# BOC_Spartan.net
KiCad netlist of a schematic drawn in Altium Designer
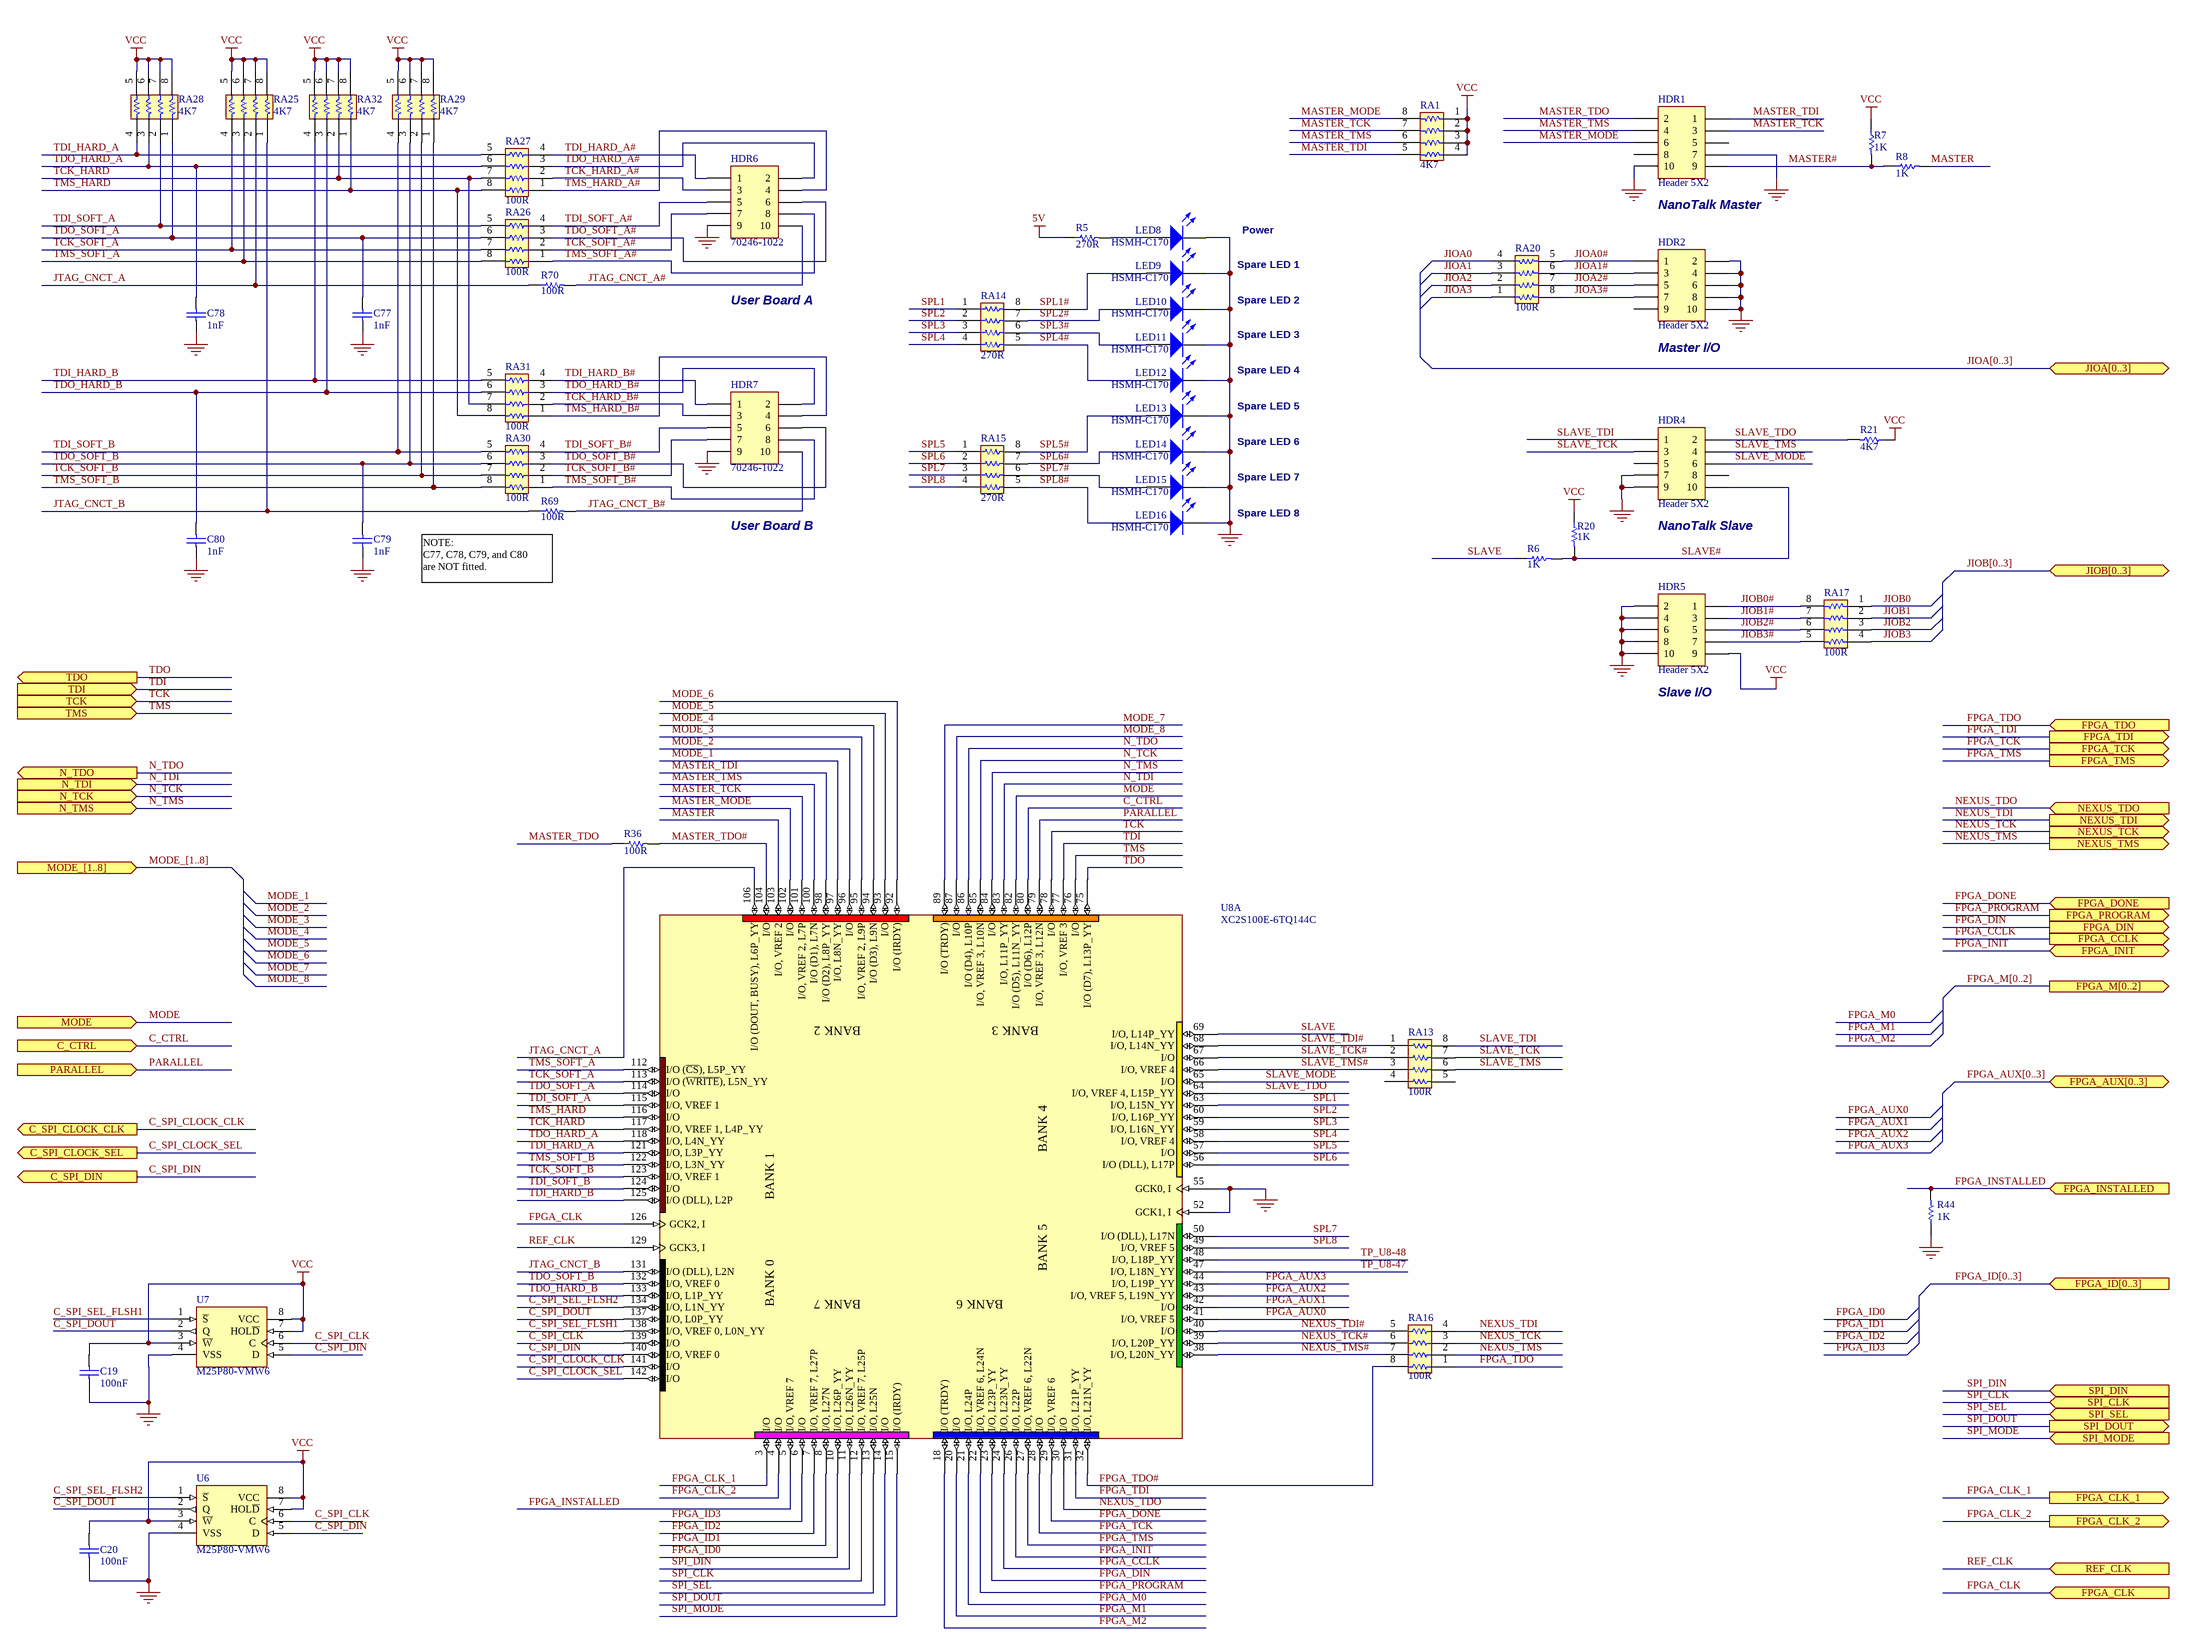
[diagram p0: BOC_Spartan.SchDoc]

(export (version "E")
  (design (tool "Eeschema 10.0.6"))
  (components
    (comp (ref "C19")
      (value "100nF")
      (footprint "Altium Nanoboard Project:CC2012-0805")
      (description "Capacitor")
      (libsource (lib "Altium Nanoboard Project") (part "CAP"))
    )
    (comp (ref "C20")
      (value "100nF")
      (footprint "Altium Nanoboard Project:CC2012-0805")
      (description "Capacitor")
      (libsource (lib "Altium Nanoboard Project") (part "CAP"))
    )
    (comp (ref "C77")
      (value "1nF")
      (footprint "Altium Nanoboard Project:CC2012-0805")
      (description "Capacitor")
      (libsource (lib "Altium Nanoboard Project") (part "CAP"))
    )
    (comp (ref "C78")
      (value "1nF")
      (footprint "Altium Nanoboard Project:CC2012-0805")
      (description "Capacitor")
      (libsource (lib "Altium Nanoboard Project") (part "CAP"))
    )
    (comp (ref "C79")
      (value "1nF")
      (footprint "Altium Nanoboard Project:CC2012-0805")
      (description "Capacitor")
      (libsource (lib "Altium Nanoboard Project") (part "CAP"))
    )
    (comp (ref "C80")
      (value "1nF")
      (footprint "Altium Nanoboard Project:CC2012-0805")
      (description "Capacitor")
      (libsource (lib "Altium Nanoboard Project") (part "CAP"))
    )
    (comp (ref "HDR1")
      (value "Header 5X2")
      (footprint "Altium Nanoboard Project:HDR2X5")
      (description "Header, 5-Pin, Dual row")
      (fields
        (field (name "MANUFACTURER") "Generic Components")
        (field (name "USAGE") "NanoTalk Master")
        (field (name "PUBLISHER") "Altium Limited")
      )
      (libsource (lib "") (part "Header 5X2_1"))
    )
    (comp (ref "HDR2")
      (value "Header 5X2")
      (footprint "Altium Nanoboard Project:HDR2X5")
      (description "Header, 5-Pin, Dual row")
      (fields
        (field (name "MANUFACTURER") "Generic Components")
        (field (name "USAGE") "Master I/O")
        (field (name "PUBLISHER") "Altium Limited")
      )
      (libsource (lib "Altium Nanoboard Project") (part "Header 5X2"))
    )
    (comp (ref "HDR4")
      (value "Header 5X2")
      (footprint "Altium Nanoboard Project:HDR2X5")
      (description "Header, 5-Pin, Dual row")
      (fields
        (field (name "MANUFACTURER") "Generic Components")
        (field (name "USAGE") "NanoTalk Slave")
        (field (name "PUBLISHER") "Altium Limited")
      )
      (libsource (lib "Altium Nanoboard Project") (part "Header 5X2"))
    )
    (comp (ref "HDR5")
      (value "Header 5X2")
      (footprint "Altium Nanoboard Project:HDR2X5")
      (description "Header, 5-Pin, Dual row")
      (fields
        (field (name "MANUFACTURER") "Generic Components")
        (field (name "USAGE") "Slave I/O")
        (field (name "PUBLISHER") "Altium Limited")
      )
      (libsource (lib "") (part "Header 5X2_1"))
    )
    (comp (ref "HDR6")
      (value "70246-1022")
      (footprint "Altium Nanoboard Project:HDR2X5_LP")
      (description "Header, 5-Pin, Dual row")
      (fields
        (field (name "MANUFACTURER") "Molex")
        (field (name "USAGE") "User Board A")
        (field (name "PUBLISHER") "Altium Limited")
      )
      (libsource (lib "Altium Nanoboard Project") (part "Header 5X2"))
    )
    (comp (ref "HDR7")
      (value "70246-1022")
      (footprint "Altium Nanoboard Project:HDR2X5_LP")
      (description "Header, 5-Pin, Dual row")
      (fields
        (field (name "MANUFACTURER") "Molex")
        (field (name "USAGE") "User Board B")
        (field (name "PUBLISHER") "Altium Limited")
      )
      (libsource (lib "Altium Nanoboard Project") (part "Header 5X2"))
    )
    (comp (ref "LED8")
      (value "HSMH-C170")
      (footprint "Altium Nanoboard Project:SMD _LED")
      (description "Typical RED GaAs SMD LED Agilent make")
      (fields (field (name "MANUFACTURER") "Generic Components") (field (name "PUBLISHER") "Altium Limited"))
      (libsource (lib "Altium Nanoboard Project") (part "HSMX-C670"))
    )
    (comp (ref "LED9")
      (value "HSMH-C170")
      (footprint "Altium Nanoboard Project:SMD _LED")
      (description "Typical RED GaAs SMD LED Agilent make")
      (fields (field (name "MANUFACTURER") "Generic Components") (field (name "PUBLISHER") "Altium Limited"))
      (libsource (lib "Altium Nanoboard Project") (part "HSMX-C670"))
    )
    (comp (ref "LED10")
      (value "HSMH-C170")
      (footprint "Altium Nanoboard Project:SMD _LED")
      (description "Typical RED GaAs SMD LED Agilent make")
      (fields (field (name "MANUFACTURER") "Generic Components") (field (name "PUBLISHER") "Altium Limited"))
      (libsource (lib "Altium Nanoboard Project") (part "HSMX-C670"))
    )
    (comp (ref "LED11")
      (value "HSMH-C170")
      (footprint "Altium Nanoboard Project:SMD _LED")
      (description "Typical RED GaAs SMD LED Agilent make")
      (fields (field (name "MANUFACTURER") "Generic Components") (field (name "PUBLISHER") "Altium Limited"))
      (libsource (lib "Altium Nanoboard Project") (part "HSMX-C670"))
    )
    (comp (ref "LED12")
      (value "HSMH-C170")
      (footprint "Altium Nanoboard Project:SMD _LED")
      (description "Typical RED GaAs SMD LED Agilent make")
      (fields (field (name "MANUFACTURER") "Generic Components") (field (name "PUBLISHER") "Altium Limited"))
      (libsource (lib "Altium Nanoboard Project") (part "HSMX-C670"))
    )
    (comp (ref "LED13")
      (value "HSMH-C170")
      (footprint "Altium Nanoboard Project:SMD _LED")
      (description "Typical RED GaAs SMD LED Agilent make")
      (fields (field (name "MANUFACTURER") "Generic Components") (field (name "PUBLISHER") "Altium Limited"))
      (libsource (lib "Altium Nanoboard Project") (part "HSMX-C670"))
    )
    (comp (ref "LED14")
      (value "HSMH-C170")
      (footprint "Altium Nanoboard Project:SMD _LED")
      (description "Typical RED GaAs SMD LED Agilent make")
      (fields (field (name "MANUFACTURER") "Generic Components") (field (name "PUBLISHER") "Altium Limited"))
      (libsource (lib "Altium Nanoboard Project") (part "HSMX-C670"))
    )
    (comp (ref "LED15")
      (value "HSMH-C170")
      (footprint "Altium Nanoboard Project:SMD _LED")
      (description "Typical RED GaAs SMD LED Agilent make")
      (fields (field (name "MANUFACTURER") "Generic Components") (field (name "PUBLISHER") "Altium Limited"))
      (libsource (lib "Altium Nanoboard Project") (part "HSMX-C670"))
    )
    (comp (ref "LED16")
      (value "HSMH-C170")
      (footprint "Altium Nanoboard Project:SMD _LED")
      (description "Typical RED GaAs SMD LED Agilent make")
      (fields (field (name "MANUFACTURER") "Generic Components") (field (name "PUBLISHER") "Altium Limited"))
      (libsource (lib "Altium Nanoboard Project") (part "HSMX-C670"))
    )
    (comp (ref "R5")
      (value "270R")
      (footprint "Altium Nanoboard Project:CC2012-0805")
      (description "Resistor")
      (libsource (lib "Altium Nanoboard Project") (part "RES"))
    )
    (comp (ref "R6")
      (value "1K")
      (footprint "Altium Nanoboard Project:CC2012-0805")
      (description "Resistor")
      (libsource (lib "Altium Nanoboard Project") (part "RES"))
    )
    (comp (ref "R7")
      (value "1K")
      (footprint "Altium Nanoboard Project:CC2012-0805")
      (description "Resistor")
      (libsource (lib "Altium Nanoboard Project") (part "RES"))
    )
    (comp (ref "R8")
      (value "1K")
      (footprint "Altium Nanoboard Project:CC2012-0805")
      (description "Resistor")
      (libsource (lib "") (part "RES_1"))
    )
    (comp (ref "R20")
      (value "1K")
      (footprint "Altium Nanoboard Project:CC2012-0805")
      (description "Resistor")
      (libsource (lib "Altium Nanoboard Project") (part "RES"))
    )
    (comp (ref "R21")
      (value "4K7")
      (footprint "Altium Nanoboard Project:CC2012-0805")
      (description "Resistor")
      (libsource (lib "Altium Nanoboard Project") (part "RES"))
    )
    (comp (ref "R36")
      (value "100R")
      (footprint "Altium Nanoboard Project:CC2012-0805")
      (description "Resistor")
      (libsource (lib "Altium Nanoboard Project") (part "RES"))
    )
    (comp (ref "R44")
      (value "1K")
      (footprint "Altium Nanoboard Project:CC2012-0805")
      (description "Resistor")
      (libsource (lib "Altium Nanoboard Project") (part "RES"))
    )
    (comp (ref "R69")
      (value "100R")
      (footprint "Altium Nanoboard Project:CC2012-0805")
      (description "Resistor")
      (libsource (lib "Altium Nanoboard Project") (part "RES"))
    )
    (comp (ref "R70")
      (value "100R")
      (footprint "Altium Nanoboard Project:CC2012-0805")
      (description "Resistor")
      (libsource (lib "Altium Nanoboard Project") (part "RES"))
    )
    (comp (ref "RA1")
      (value "4K7")
      (footprint "Altium Nanoboard Project:MNR34")
      (description "3216x4 Resistor Array")
      (libsource (lib "") (part "MNR34_3"))
    )
    (comp (ref "RA13")
      (value "100R")
      (footprint "Altium Nanoboard Project:MNR34")
      (description "3216x4 Resistor Array")
      (libsource (lib "") (part "MNR34_2"))
    )
    (comp (ref "RA14")
      (value "270R")
      (footprint "Altium Nanoboard Project:MNR34")
      (description "3216x4 Resistor Array")
      (libsource (lib "") (part "MNR34_2"))
    )
    (comp (ref "RA15")
      (value "270R")
      (footprint "Altium Nanoboard Project:MNR34")
      (description "3216x4 Resistor Array")
      (libsource (lib "") (part "MNR34_2"))
    )
    (comp (ref "RA16")
      (value "100R")
      (footprint "Altium Nanoboard Project:MNR34")
      (description "3216x4 Resistor Array")
      (libsource (lib "Altium Nanoboard Project") (part "MNR34"))
    )
    (comp (ref "RA17")
      (value "100R")
      (footprint "Altium Nanoboard Project:MNR34")
      (description "3216x4 Resistor Array")
      (libsource (lib "") (part "MNR34_3"))
    )
    (comp (ref "RA20")
      (value "100R")
      (footprint "Altium Nanoboard Project:MNR34")
      (description "3216x4 Resistor Array")
      (libsource (lib "") (part "MNR34_4"))
    )
    (comp (ref "RA25")
      (value "4K7")
      (footprint "Altium Nanoboard Project:MNR34")
      (description "3216x4 Resistor Array")
      (libsource (lib "") (part "MNR34_2"))
    )
    (comp (ref "RA26")
      (value "100R")
      (footprint "Altium Nanoboard Project:MNR34")
      (description "3216x4 Resistor Array")
      (libsource (lib "") (part "MNR34_1"))
    )
    (comp (ref "RA27")
      (value "100R")
      (footprint "Altium Nanoboard Project:MNR34")
      (description "3216x4 Resistor Array")
      (libsource (lib "") (part "MNR34_1"))
    )
    (comp (ref "RA28")
      (value "4K7")
      (footprint "Altium Nanoboard Project:MNR34")
      (description "3216x4 Resistor Array")
      (libsource (lib "") (part "MNR34_2"))
    )
    (comp (ref "RA29")
      (value "4K7")
      (footprint "Altium Nanoboard Project:MNR34")
      (description "3216x4 Resistor Array")
      (libsource (lib "") (part "MNR34_2"))
    )
    (comp (ref "RA30")
      (value "100R")
      (footprint "Altium Nanoboard Project:MNR34")
      (description "3216x4 Resistor Array")
      (libsource (lib "") (part "MNR34_1"))
    )
    (comp (ref "RA31")
      (value "100R")
      (footprint "Altium Nanoboard Project:MNR34")
      (description "3216x4 Resistor Array")
      (libsource (lib "") (part "MNR34_1"))
    )
    (comp (ref "RA32")
      (value "4K7")
      (footprint "Altium Nanoboard Project:MNR34")
      (description "3216x4 Resistor Array")
      (libsource (lib "") (part "MNR34_2"))
    )
    (comp (ref "U6")
      (value "M25P80-VMW6")
      (footprint "Altium Nanoboard Project:SO8_MW/SO8_MN")
      (description "8 Mbit Flash Serial Prom")
      (libsource (lib "Altium Nanoboard Project") (part "M25P10-VMN6"))
    )
    (comp (ref "U7")
      (value "M25P80-VMW6")
      (footprint "Altium Nanoboard Project:SO8_MW/SO8_MN")
      (description "8 Mbit Flash Serial Prom")
      (libsource (lib "Altium Nanoboard Project") (part "M25P20-VMN6"))
    )
    (comp (ref "U8")
      (value "XC2S100E-6TQ144C")
      (footprint "Altium Nanoboard Project:TQ144")
      (description "Spartan-IIE 1.8V FPGA, 144-Pin TQFP, Standard Performance, Commercial Grade")
      (fields (field (name "MANUFACTURER") "Xilinx") (field (name "PUBLISHER") "Altium Limited"))
      (libsource (lib "Altium Nanoboard Project") (part "XC2S100E-6TQ144C"))
    )
  )
  (nets
    (net (code "1") (name "/C_CTRL") (class "Default")
      (node (ref "U8") (pin "80") (pinfunction "I/O_(D6),_L12P_80") (pintype "bidirectional"))
    )
    (net (code "2") (name "/C_SPI_CLK") (class "Default")
      (node (ref "U6") (pin "6") (pinfunction "C_6") (pintype "input"))
      (node (ref "U7") (pin "6") (pinfunction "C_6") (pintype "input"))
      (node (ref "U8") (pin "139") (pinfunction "I/O_139") (pintype "bidirectional"))
    )
    (net (code "3") (name "/C_SPI_CLOCK_CLK") (class "Default")
      (node (ref "U8") (pin "141") (pinfunction "I/O_141") (pintype "bidirectional"))
    )
    (net (code "4") (name "/C_SPI_CLOCK_SEL") (class "Default")
      (node (ref "U8") (pin "142") (pinfunction "I/O_142") (pintype "bidirectional"))
    )
    (net (code "5") (name "/C_SPI_DIN") (class "Default")
      (node (ref "U6") (pin "5") (pinfunction "D_5") (pintype "input"))
      (node (ref "U7") (pin "5") (pinfunction "D_5") (pintype "input"))
      (node (ref "U8") (pin "140") (pinfunction "I/O,_VREF_0_140") (pintype "bidirectional"))
    )
    (net (code "6") (name "/C_SPI_DOUT") (class "Default")
      (node (ref "U6") (pin "2") (pinfunction "Q_2") (pintype "output"))
      (node (ref "U7") (pin "2") (pinfunction "Q_2") (pintype "output"))
      (node (ref "U8") (pin "137") (pinfunction "I/O,_L0P_YY_137") (pintype "bidirectional"))
    )
    (net (code "7") (name "/C_SPI_SEL_FLSH1") (class "Default")
      (node (ref "U7") (pin "1") (pinfunction "~{S}_1") (pintype "input"))
      (node (ref "U8") (pin "138") (pinfunction "I/O,_VREF_0,_L0N_YY_138") (pintype "bidirectional"))
    )
    (net (code "8") (name "/C_SPI_SEL_FLSH2") (class "Default")
      (node (ref "U6") (pin "1") (pinfunction "~{S}_1") (pintype "input"))
      (node (ref "U8") (pin "134") (pinfunction "I/O,_L1N_YY_134") (pintype "bidirectional"))
    )
    (net (code "9") (name "/FPGA_AUX0") (class "Default")
      (node (ref "U8") (pin "41") (pinfunction "I/O,_VREF_5_41") (pintype "bidirectional"))
    )
    (net (code "10") (name "/FPGA_AUX1") (class "Default")
      (node (ref "U8") (pin "42") (pinfunction "I/O_42") (pintype "bidirectional"))
    )
    (net (code "11") (name "/FPGA_AUX2") (class "Default")
      (node (ref "U8") (pin "43") (pinfunction "I/O,_VREF_5,_L19N_YY_43") (pintype "bidirectional"))
    )
    (net (code "12") (name "/FPGA_AUX3") (class "Default")
      (node (ref "U8") (pin "44") (pinfunction "I/O,_L19P_YY_44") (pintype "bidirectional"))
    )
    (net (code "14") (name "/FPGA_CCLK") (class "Default")
      (node (ref "U8") (pin "24") (pinfunction "I/O,_L23N_YY_24") (pintype "bidirectional"))
    )
    (net (code "15") (name "/FPGA_CLK") (class "Default")
      (node (ref "U8") (pin "126") (pinfunction "GCK2,_I_126") (pintype "input"))
    )
    (net (code "16") (name "/FPGA_CLK_1") (class "Default")
      (node (ref "U8") (pin "3") (pinfunction "I/O_3") (pintype "bidirectional"))
    )
    (net (code "17") (name "/FPGA_CLK_2") (class "Default")
      (node (ref "U8") (pin "4") (pinfunction "I/O_4") (pintype "bidirectional"))
    )
    (net (code "18") (name "/FPGA_DIN") (class "Default")
      (node (ref "U8") (pin "23") (pinfunction "I/O,_L23P_YY_23") (pintype "bidirectional"))
    )
    (net (code "19") (name "/FPGA_DONE") (class "Default")
      (node (ref "U8") (pin "29") (pinfunction "I/O,_VREF_6_29") (pintype "bidirectional"))
    )
    (net (code "20") (name "/FPGA_ID0") (class "Default")
      (node (ref "U8") (pin "10") (pinfunction "I/O,_L26P_YY_10") (pintype "bidirectional"))
    )
    (net (code "21") (name "/FPGA_ID1") (class "Default")
      (node (ref "U8") (pin "8") (pinfunction "I/O,_L27N_8") (pintype "bidirectional"))
    )
    (net (code "22") (name "/FPGA_ID2") (class "Default")
      (node (ref "U8") (pin "7") (pinfunction "I/O,_VREF_7,_L27P_7") (pintype "bidirectional"))
    )
    (net (code "23") (name "/FPGA_ID3") (class "Default")
      (node (ref "U8") (pin "6") (pinfunction "I/O_6") (pintype "bidirectional"))
    )
    (net (code "25") (name "/FPGA_INIT") (class "Default")
      (node (ref "U8") (pin "26") (pinfunction "I/O,_L22P_26") (pintype "bidirectional"))
    )
    (net (code "26") (name "/FPGA_INSTALLED") (class "Default")
      (node (ref "R44") (pin "2") (pinfunction "2_2") (pintype "passive"))
      (node (ref "U8") (pin "5") (pinfunction "I/O,_VREF_7_5") (pintype "bidirectional"))
    )
    (net (code "27") (name "/FPGA_M0") (class "Default")
      (node (ref "U8") (pin "21") (pinfunction "I/O,_L24P_21") (pintype "bidirectional"))
    )
    (net (code "28") (name "/FPGA_M1") (class "Default")
      (node (ref "U8") (pin "20") (pinfunction "I/O_20") (pintype "bidirectional"))
    )
    (net (code "29") (name "/FPGA_M2") (class "Default")
      (node (ref "U8") (pin "18") (pinfunction "I/O_(TRDY)_18") (pintype "bidirectional"))
    )
    (net (code "31") (name "/FPGA_PROGRAM") (class "Default")
      (node (ref "U8") (pin "22") (pinfunction "I/O,_VREF_6,_L24N_22") (pintype "bidirectional"))
    )
    (net (code "32") (name "/FPGA_TCK") (class "Default")
      (node (ref "U8") (pin "28") (pinfunction "I/O_28") (pintype "bidirectional"))
    )
    (net (code "33") (name "/FPGA_TDI") (class "Default")
      (node (ref "U8") (pin "31") (pinfunction "I/O,_L21P_YY_31") (pintype "bidirectional"))
    )
    (net (code "34") (name "/FPGA_TDO") (class "Default") (node (ref "RA16") (pin "1") (pintype "passive")))
    (net (code "35") (name "/FPGA_TDO#") (class "Default")
      (node (ref "RA16") (pin "8") (pintype "passive"))
      (node (ref "U8") (pin "32") (pinfunction "I/O,_L21N_YY_32") (pintype "bidirectional"))
    )
    (net (code "36") (name "/FPGA_TMS") (class "Default")
      (node (ref "U8") (pin "27") (pinfunction "I/O,_VREF_6,_L22N_27") (pintype "bidirectional"))
    )
    (net (code "37") (name "/JIOA0") (class "Default") (node (ref "RA20") (pin "4") (pintype "passive")))
    (net (code "38") (name "/JIOA0#") (class "Default")
      (node (ref "HDR2") (pin "1") (pinfunction "1_1") (pintype "passive"))
      (node (ref "RA20") (pin "5") (pintype "passive"))
    )
    (net (code "39") (name "/JIOA1") (class "Default") (node (ref "RA20") (pin "3") (pintype "passive")))
    (net (code "40") (name "/JIOA1#") (class "Default")
      (node (ref "HDR2") (pin "3") (pinfunction "3_3") (pintype "passive"))
      (node (ref "RA20") (pin "6") (pintype "passive"))
    )
    (net (code "41") (name "/JIOA2") (class "Default") (node (ref "RA20") (pin "2") (pintype "passive")))
    (net (code "42") (name "/JIOA2#") (class "Default")
      (node (ref "HDR2") (pin "5") (pinfunction "5_5") (pintype "passive"))
      (node (ref "RA20") (pin "7") (pintype "passive"))
    )
    (net (code "43") (name "/JIOA3") (class "Default") (node (ref "RA20") (pin "1") (pintype "passive")))
    (net (code "44") (name "/JIOA3#") (class "Default")
      (node (ref "HDR2") (pin "7") (pinfunction "7_7") (pintype "passive"))
      (node (ref "RA20") (pin "8") (pintype "passive"))
    )
    (net (code "46") (name "/JIOB0") (class "Default") (node (ref "RA17") (pin "1") (pintype "passive")))
    (net (code "47") (name "/JIOB0#") (class "Default")
      (node (ref "HDR5") (pin "1") (pinfunction "1_1") (pintype "passive"))
      (node (ref "RA17") (pin "8") (pintype "passive"))
    )
    (net (code "48") (name "/JIOB1") (class "Default") (node (ref "RA17") (pin "2") (pintype "passive")))
    (net (code "49") (name "/JIOB1#") (class "Default")
      (node (ref "HDR5") (pin "3") (pinfunction "3_3") (pintype "passive"))
      (node (ref "RA17") (pin "7") (pintype "passive"))
    )
    (net (code "50") (name "/JIOB2") (class "Default") (node (ref "RA17") (pin "3") (pintype "passive")))
    (net (code "51") (name "/JIOB2#") (class "Default")
      (node (ref "HDR5") (pin "5") (pinfunction "5_5") (pintype "passive"))
      (node (ref "RA17") (pin "6") (pintype "passive"))
    )
    (net (code "52") (name "/JIOB3") (class "Default") (node (ref "RA17") (pin "4") (pintype "passive")))
    (net (code "53") (name "/JIOB3#") (class "Default")
      (node (ref "HDR5") (pin "7") (pinfunction "7_7") (pintype "passive"))
      (node (ref "RA17") (pin "5") (pintype "passive"))
    )
    (net (code "55") (name "/JTAG_CNCT_A") (class "Default")
      (node (ref "R70") (pin "1") (pinfunction "1_1") (pintype "passive"))
      (node (ref "RA25") (pin "2") (pintype "passive"))
      (node (ref "U8") (pin "106") (pinfunction "I/O_(DOUT,_BUSY),_L6P_YY_106") (pintype "bidirectional"))
    )
    (net (code "56") (name "/JTAG_CNCT_A#") (class "Default")
      (node (ref "HDR6") (pin "10") (pinfunction "10_10") (pintype "passive"))
      (node (ref "R70") (pin "2") (pinfunction "2_2") (pintype "passive"))
    )
    (net (code "57") (name "/JTAG_CNCT_B") (class "Default")
      (node (ref "R69") (pin "1") (pinfunction "1_1") (pintype "passive"))
      (node (ref "RA25") (pin "1") (pintype "passive"))
      (node (ref "U8") (pin "131") (pinfunction "I/O_(DLL),_L2N_131") (pintype "bidirectional"))
    )
    (net (code "58") (name "/JTAG_CNCT_B#") (class "Default")
      (node (ref "HDR7") (pin "10") (pinfunction "10_10") (pintype "passive"))
      (node (ref "R69") (pin "2") (pinfunction "2_2") (pintype "passive"))
    )
    (net (code "59") (name "/MASTER") (class "Default")
      (node (ref "R8") (pin "2") (pinfunction "2_2") (pintype "passive"))
      (node (ref "U8") (pin "103") (pinfunction "I/O,_VREF_2_103") (pintype "bidirectional"))
    )
    (net (code "60") (name "/MASTER#") (class "Default")
      (node (ref "HDR1") (pin "9") (pinfunction "9_9") (pintype "passive"))
      (node (ref "R7") (pin "2") (pinfunction "2_2") (pintype "passive"))
      (node (ref "R8") (pin "1") (pinfunction "1_1") (pintype "passive"))
    )
    (net (code "61") (name "/MASTER_MODE") (class "Default")
      (node (ref "HDR1") (pin "6") (pinfunction "6_6") (pintype "passive"))
      (node (ref "RA1") (pin "8") (pintype "passive"))
      (node (ref "U8") (pin "102") (pinfunction "I/O_102") (pintype "bidirectional"))
    )
    (net (code "62") (name "/MASTER_TCK") (class "Default")
      (node (ref "HDR1") (pin "3") (pinfunction "3_3") (pintype "passive"))
      (node (ref "RA1") (pin "7") (pintype "passive"))
      (node (ref "U8") (pin "101") (pinfunction "I/O,_VREF_2,_L7P_101") (pintype "bidirectional"))
    )
    (net (code "63") (name "/MASTER_TDI") (class "Default")
      (node (ref "HDR1") (pin "1") (pinfunction "1_1") (pintype "passive"))
      (node (ref "RA1") (pin "5") (pintype "passive"))
      (node (ref "U8") (pin "98") (pinfunction "I/O_(D2),_L8P_YY_98") (pintype "bidirectional"))
    )
    (net (code "64") (name "/MASTER_TDO") (class "Default")
      (node (ref "HDR1") (pin "2") (pinfunction "2_2") (pintype "passive"))
      (node (ref "R36") (pin "1") (pinfunction "1_1") (pintype "passive"))
    )
    (net (code "65") (name "/MASTER_TDO#") (class "Default")
      (node (ref "R36") (pin "2") (pinfunction "2_2") (pintype "passive"))
      (node (ref "U8") (pin "104") (pinfunction "I/O_104") (pintype "bidirectional"))
    )
    (net (code "66") (name "/MASTER_TMS") (class "Default")
      (node (ref "HDR1") (pin "4") (pinfunction "4_4") (pintype "passive"))
      (node (ref "RA1") (pin "6") (pintype "passive"))
      (node (ref "U8") (pin "100") (pinfunction "I/O_(D1),_L7N_100") (pintype "bidirectional"))
    )
    (net (code "67") (name "/MODE") (class "Default")
      (node (ref "U8") (pin "82") (pinfunction "I/O_(D5),_L11N_YY_82") (pintype "bidirectional"))
    )
    (net (code "68") (name "/MODE_1") (class "Default")
      (node (ref "U8") (pin "97") (pinfunction "I/O,_L8N_YY_97") (pintype "bidirectional"))
    )
    (net (code "69") (name "/MODE_2") (class "Default")
      (node (ref "U8") (pin "96") (pinfunction "I/O_96") (pintype "bidirectional"))
    )
    (net (code "70") (name "/MODE_3") (class "Default")
      (node (ref "U8") (pin "95") (pinfunction "I/O,_VREF_2,_L9P_95") (pintype "bidirectional"))
    )
    (net (code "71") (name "/MODE_4") (class "Default")
      (node (ref "U8") (pin "94") (pinfunction "I/O_(D3),_L9N_94") (pintype "bidirectional"))
    )
    (net (code "72") (name "/MODE_5") (class "Default")
      (node (ref "U8") (pin "93") (pinfunction "I/O_93") (pintype "bidirectional"))
    )
    (net (code "73") (name "/MODE_6") (class "Default")
      (node (ref "U8") (pin "92") (pinfunction "I/O_(IRDY)_92") (pintype "bidirectional"))
    )
    (net (code "74") (name "/MODE_7") (class "Default")
      (node (ref "U8") (pin "89") (pinfunction "I/O_(TRDY)_89") (pintype "bidirectional"))
    )
    (net (code "75") (name "/MODE_8") (class "Default")
      (node (ref "U8") (pin "87") (pinfunction "I/O_87") (pintype "bidirectional"))
    )
    (net (code "77") (name "/NEXUS_TCK") (class "Default") (node (ref "RA16") (pin "3") (pintype "passive")))
    (net (code "78") (name "/NEXUS_TCK#") (class "Default")
      (node (ref "RA16") (pin "6") (pintype "passive"))
      (node (ref "U8") (pin "39") (pinfunction "I/O,_L20P_YY_39") (pintype "bidirectional"))
    )
    (net (code "79") (name "/NEXUS_TDI") (class "Default") (node (ref "RA16") (pin "4") (pintype "passive")))
    (net (code "80") (name "/NEXUS_TDI#") (class "Default")
      (node (ref "RA16") (pin "5") (pintype "passive"))
      (node (ref "U8") (pin "40") (pinfunction "I/O_40") (pintype "bidirectional"))
    )
    (net (code "81") (name "/NEXUS_TDO") (class "Default")
      (node (ref "U8") (pin "30") (pinfunction "I/O_30") (pintype "bidirectional"))
    )
    (net (code "82") (name "/NEXUS_TMS") (class "Default") (node (ref "RA16") (pin "2") (pintype "passive")))
    (net (code "83") (name "/NEXUS_TMS#") (class "Default")
      (node (ref "RA16") (pin "7") (pintype "passive"))
      (node (ref "U8") (pin "38") (pinfunction "I/O,_L20N_YY_38") (pintype "bidirectional"))
    )
    (net (code "84") (name "/N_TCK") (class "Default")
      (node (ref "U8") (pin "85") (pinfunction "I/O,_VREF_3,_L10N_85") (pintype "bidirectional"))
    )
    (net (code "85") (name "/N_TDI") (class "Default")
      (node (ref "U8") (pin "83") (pinfunction "I/O,_L11P_YY_83") (pintype "bidirectional"))
    )
    (net (code "86") (name "/N_TDO") (class "Default")
      (node (ref "U8") (pin "86") (pinfunction "I/O_(D4),_L10P_86") (pintype "bidirectional"))
    )
    (net (code "87") (name "/N_TMS") (class "Default")
      (node (ref "U8") (pin "84") (pinfunction "I/O_84") (pintype "bidirectional"))
    )
    (net (code "88") (name "/PARALLEL") (class "Default")
      (node (ref "U8") (pin "79") (pinfunction "I/O,_VREF_3,_L12N_79") (pintype "bidirectional"))
    )
    (net (code "89") (name "/REF_CLK") (class "Default")
      (node (ref "U8") (pin "129") (pinfunction "GCK3,_I_129") (pintype "input"))
    )
    (net (code "90") (name "/SLAVE") (class "Default")
      (node (ref "R6") (pin "1") (pinfunction "1_1") (pintype "passive"))
      (node (ref "U8") (pin "69") (pinfunction "I/O,_L14P_YY_69") (pintype "bidirectional"))
    )
    (net (code "91") (name "/SLAVE#") (class "Default")
      (node (ref "HDR4") (pin "10") (pinfunction "10_10") (pintype "passive"))
      (node (ref "R20") (pin "2") (pinfunction "2_2") (pintype "passive"))
      (node (ref "R6") (pin "2") (pinfunction "2_2") (pintype "passive"))
    )
    (net (code "92") (name "/SLAVE_MODE") (class "Default")
      (node (ref "HDR4") (pin "6") (pinfunction "6_6") (pintype "passive"))
      (node (ref "U8") (pin "65") (pinfunction "I/O_65") (pintype "bidirectional"))
    )
    (net (code "93") (name "/SLAVE_TCK") (class "Default")
      (node (ref "HDR4") (pin "3") (pinfunction "3_3") (pintype "passive"))
      (node (ref "RA13") (pin "7") (pintype "passive"))
    )
    (net (code "94") (name "/SLAVE_TCK#") (class "Default")
      (node (ref "RA13") (pin "2") (pintype "passive"))
      (node (ref "U8") (pin "67") (pinfunction "I/O_67") (pintype "bidirectional"))
    )
    (net (code "95") (name "/SLAVE_TDI") (class "Default")
      (node (ref "HDR4") (pin "1") (pinfunction "1_1") (pintype "passive"))
      (node (ref "RA13") (pin "8") (pintype "passive"))
    )
    (net (code "96") (name "/SLAVE_TDI#") (class "Default")
      (node (ref "RA13") (pin "1") (pintype "passive"))
      (node (ref "U8") (pin "68") (pinfunction "I/O,_L14N_YY_68") (pintype "bidirectional"))
    )
    (net (code "97") (name "/SLAVE_TDO") (class "Default")
      (node (ref "HDR4") (pin "2") (pinfunction "2_2") (pintype "passive"))
      (node (ref "R21") (pin "2") (pinfunction "2_2") (pintype "passive"))
      (node (ref "U8") (pin "64") (pinfunction "I/O,_VREF_4,_L15P_YY_64") (pintype "bidirectional"))
    )
    (net (code "98") (name "/SLAVE_TMS") (class "Default")
      (node (ref "HDR4") (pin "4") (pinfunction "4_4") (pintype "passive"))
      (node (ref "RA13") (pin "6") (pintype "passive"))
    )
    (net (code "99") (name "/SLAVE_TMS#") (class "Default")
      (node (ref "RA13") (pin "3") (pintype "passive"))
      (node (ref "U8") (pin "66") (pinfunction "I/O,_VREF_4_66") (pintype "bidirectional"))
    )
    (net (code "100") (name "/SPI_CLK") (class "Default")
      (node (ref "U8") (pin "12") (pinfunction "I/O,_VREF_7,_L25P_12") (pintype "bidirectional"))
    )
    (net (code "101") (name "/SPI_DIN") (class "Default")
      (node (ref "U8") (pin "11") (pinfunction "I/O,_L26N_YY_11") (pintype "bidirectional"))
    )
    (net (code "102") (name "/SPI_DOUT") (class "Default")
      (node (ref "U8") (pin "14") (pinfunction "I/O_14") (pintype "bidirectional"))
    )
    (net (code "103") (name "/SPI_MODE") (class "Default")
      (node (ref "U8") (pin "15") (pinfunction "I/O_(IRDY)_15") (pintype "bidirectional"))
    )
    (net (code "104") (name "/SPI_SEL") (class "Default")
      (node (ref "U8") (pin "13") (pinfunction "I/O,_L25N_13") (pintype "bidirectional"))
    )
    (net (code "105") (name "/SPL1") (class "Default")
      (node (ref "RA14") (pin "1") (pintype "passive"))
      (node (ref "U8") (pin "63") (pinfunction "I/O,_L15N_YY_63") (pintype "bidirectional"))
    )
    (net (code "106") (name "/SPL1#") (class "Default")
      (node (ref "LED9") (pin "1") (pinfunction "A_1") (pintype "passive"))
      (node (ref "RA14") (pin "8") (pintype "passive"))
    )
    (net (code "107") (name "/SPL2") (class "Default")
      (node (ref "RA14") (pin "2") (pintype "passive"))
      (node (ref "U8") (pin "60") (pinfunction "I/O,_L16P_YY_60") (pintype "bidirectional"))
    )
    (net (code "108") (name "/SPL2#") (class "Default")
      (node (ref "LED10") (pin "1") (pinfunction "A_1") (pintype "passive"))
      (node (ref "RA14") (pin "7") (pintype "passive"))
    )
    (net (code "109") (name "/SPL3") (class "Default")
      (node (ref "RA14") (pin "3") (pintype "passive"))
      (node (ref "U8") (pin "59") (pinfunction "I/O,_L16N_YY_59") (pintype "bidirectional"))
    )
    (net (code "110") (name "/SPL3#") (class "Default")
      (node (ref "LED11") (pin "1") (pinfunction "A_1") (pintype "passive"))
      (node (ref "RA14") (pin "6") (pintype "passive"))
    )
    (net (code "111") (name "/SPL4") (class "Default")
      (node (ref "RA14") (pin "4") (pintype "passive"))
      (node (ref "U8") (pin "58") (pinfunction "I/O,_VREF_4_58") (pintype "bidirectional"))
    )
    (net (code "112") (name "/SPL4#") (class "Default")
      (node (ref "LED12") (pin "1") (pinfunction "A_1") (pintype "passive"))
      (node (ref "RA14") (pin "5") (pintype "passive"))
    )
    (net (code "113") (name "/SPL5") (class "Default")
      (node (ref "RA15") (pin "1") (pintype "passive"))
      (node (ref "U8") (pin "57") (pinfunction "I/O_57") (pintype "bidirectional"))
    )
    (net (code "114") (name "/SPL5#") (class "Default")
      (node (ref "LED13") (pin "1") (pinfunction "A_1") (pintype "passive"))
      (node (ref "RA15") (pin "8") (pintype "passive"))
    )
    (net (code "115") (name "/SPL6") (class "Default")
      (node (ref "RA15") (pin "2") (pintype "passive"))
      (node (ref "U8") (pin "56") (pinfunction "I/O_(DLL),_L17P_56") (pintype "bidirectional"))
    )
    (net (code "116") (name "/SPL6#") (class "Default")
      (node (ref "LED14") (pin "1") (pinfunction "A_1") (pintype "passive"))
      (node (ref "RA15") (pin "7") (pintype "passive"))
    )
    (net (code "117") (name "/SPL7") (class "Default")
      (node (ref "RA15") (pin "3") (pintype "passive"))
      (node (ref "U8") (pin "50") (pinfunction "I/O_(DLL),_L17N_50") (pintype "bidirectional"))
    )
    (net (code "118") (name "/SPL7#") (class "Default")
      (node (ref "LED15") (pin "1") (pinfunction "A_1") (pintype "passive"))
      (node (ref "RA15") (pin "6") (pintype "passive"))
    )
    (net (code "119") (name "/SPL8") (class "Default")
      (node (ref "RA15") (pin "4") (pintype "passive"))
      (node (ref "U8") (pin "49") (pinfunction "I/O,_VREF_5_49") (pintype "bidirectional"))
    )
    (net (code "120") (name "/SPL8#") (class "Default")
      (node (ref "LED16") (pin "1") (pinfunction "A_1") (pintype "passive"))
      (node (ref "RA15") (pin "5") (pintype "passive"))
    )
    (net (code "121") (name "/TCK") (class "Default")
      (node (ref "U8") (pin "78") (pinfunction "I/O_78") (pintype "bidirectional"))
    )
    (net (code "122") (name "/TCK_HARD") (class "Default")
      (node (ref "RA27") (pin "7") (pintype "passive"))
      (node (ref "RA31") (pin "7") (pintype "passive"))
      (node (ref "RA32") (pin "2") (pintype "passive"))
      (node (ref "U8") (pin "117") (pinfunction "I/O,_VREF_1,_L4P_YY_117") (pintype "bidirectional"))
    )
    (net (code "123") (name "/TCK_HARD_A#") (class "Default")
      (node (ref "HDR6") (pin "3") (pinfunction "3_3") (pintype "passive"))
      (node (ref "RA27") (pin "2") (pintype "passive"))
    )
    (net (code "124") (name "/TCK_HARD_B#") (class "Default")
      (node (ref "HDR7") (pin "3") (pinfunction "3_3") (pintype "passive"))
      (node (ref "RA31") (pin "2") (pintype "passive"))
    )
    (net (code "125") (name "/TCK_SOFT_A") (class "Default")
      (node (ref "RA25") (pin "4") (pintype "passive"))
      (node (ref "RA26") (pin "7") (pintype "passive"))
      (node (ref "U8") (pin "113") (pinfunction "I/O_(~{WRITE}),_L5N_YY_113") (pintype "bidirectional"))
    )
    (net (code "126") (name "/TCK_SOFT_A#") (class "Default")
      (node (ref "HDR6") (pin "7") (pinfunction "7_7") (pintype "passive"))
      (node (ref "RA26") (pin "2") (pintype "passive"))
    )
    (net (code "127") (name "/TCK_SOFT_B") (class "Default")
      (node (ref "RA29") (pin "2") (pintype "passive"))
      (node (ref "RA30") (pin "7") (pintype "passive"))
      (node (ref "U8") (pin "123") (pinfunction "I/O,_VREF_1_123") (pintype "bidirectional"))
    )
    (net (code "128") (name "/TCK_SOFT_B#") (class "Default")
      (node (ref "HDR7") (pin "7") (pinfunction "7_7") (pintype "passive"))
      (node (ref "RA30") (pin "2") (pintype "passive"))
    )
    (net (code "129") (name "/TDI") (class "Default")
      (node (ref "U8") (pin "77") (pinfunction "I/O,_VREF_3_77") (pintype "bidirectional"))
    )
    (net (code "130") (name "/TDI_HARD_A") (class "Default")
      (node (ref "RA27") (pin "5") (pintype "passive"))
      (node (ref "RA28") (pin "4") (pintype "passive"))
      (node (ref "U8") (pin "121") (pinfunction "I/O,_L3P_YY_121") (pintype "bidirectional"))
    )
    (net (code "131") (name "/TDI_HARD_A#") (class "Default")
      (node (ref "HDR6") (pin "1") (pinfunction "1_1") (pintype "passive"))
      (node (ref "RA27") (pin "4") (pintype "passive"))
    )
    (net (code "132") (name "/TDI_HARD_B") (class "Default")
      (node (ref "RA31") (pin "5") (pintype "passive"))
      (node (ref "RA32") (pin "4") (pintype "passive"))
      (node (ref "U8") (pin "125") (pinfunction "I/O_(DLL),_L2P_125") (pintype "bidirectional"))
    )
    (net (code "133") (name "/TDI_HARD_B#") (class "Default")
      (node (ref "HDR7") (pin "1") (pinfunction "1_1") (pintype "passive"))
      (node (ref "RA31") (pin "4") (pintype "passive"))
    )
    (net (code "134") (name "/TDI_SOFT_A") (class "Default")
      (node (ref "RA26") (pin "5") (pintype "passive"))
      (node (ref "RA28") (pin "2") (pintype "passive"))
      (node (ref "U8") (pin "115") (pinfunction "I/O,_VREF_1_115") (pintype "bidirectional"))
    )
    (net (code "135") (name "/TDI_SOFT_A#") (class "Default")
      (node (ref "HDR6") (pin "5") (pinfunction "5_5") (pintype "passive"))
      (node (ref "RA26") (pin "4") (pintype "passive"))
    )
    (net (code "136") (name "/TDI_SOFT_B") (class "Default")
      (node (ref "RA29") (pin "4") (pintype "passive"))
      (node (ref "RA30") (pin "5") (pintype "passive"))
      (node (ref "U8") (pin "124") (pinfunction "I/O_124") (pintype "bidirectional"))
    )
    (net (code "137") (name "/TDI_SOFT_B#") (class "Default")
      (node (ref "HDR7") (pin "5") (pinfunction "5_5") (pintype "passive"))
      (node (ref "RA30") (pin "4") (pintype "passive"))
    )
    (net (code "138") (name "/TDO") (class "Default")
      (node (ref "U8") (pin "75") (pinfunction "I/O_(D7),_L13P_YY_75") (pintype "bidirectional"))
    )
    (net (code "139") (name "/TDO_HARD_A") (class "Default")
      (node (ref "C78") (pin "1") (pinfunction "1_1") (pintype "passive"))
      (node (ref "RA27") (pin "6") (pintype "passive"))
      (node (ref "RA28") (pin "3") (pintype "passive"))
      (node (ref "U8") (pin "118") (pinfunction "I/O,_L4N_YY_118") (pintype "bidirectional"))
    )
    (net (code "140") (name "/TDO_HARD_A#") (class "Default")
      (node (ref "HDR6") (pin "2") (pinfunction "2_2") (pintype "passive"))
      (node (ref "RA27") (pin "3") (pintype "passive"))
    )
    (net (code "141") (name "/TDO_HARD_B") (class "Default")
      (node (ref "C80") (pin "1") (pinfunction "1_1") (pintype "passive"))
      (node (ref "RA31") (pin "6") (pintype "passive"))
      (node (ref "RA32") (pin "3") (pintype "passive"))
      (node (ref "U8") (pin "133") (pinfunction "I/O,_L1P_YY_133") (pintype "bidirectional"))
    )
    (net (code "142") (name "/TDO_HARD_B#") (class "Default")
      (node (ref "HDR7") (pin "2") (pinfunction "2_2") (pintype "passive"))
      (node (ref "RA31") (pin "3") (pintype "passive"))
    )
    (net (code "143") (name "/TDO_SOFT_A") (class "Default")
      (node (ref "C77") (pin "1") (pinfunction "1_1") (pintype "passive"))
      (node (ref "RA26") (pin "6") (pintype "passive"))
      (node (ref "RA28") (pin "1") (pintype "passive"))
      (node (ref "U8") (pin "114") (pinfunction "I/O_114") (pintype "bidirectional"))
    )
    (net (code "144") (name "/TDO_SOFT_A#") (class "Default")
      (node (ref "HDR6") (pin "6") (pinfunction "6_6") (pintype "passive"))
      (node (ref "RA26") (pin "3") (pintype "passive"))
    )
    (net (code "145") (name "/TDO_SOFT_B") (class "Default")
      (node (ref "C79") (pin "1") (pinfunction "1_1") (pintype "passive"))
      (node (ref "RA29") (pin "3") (pintype "passive"))
      (node (ref "RA30") (pin "6") (pintype "passive"))
      (node (ref "U8") (pin "132") (pinfunction "I/O,_VREF_0_132") (pintype "bidirectional"))
    )
    (net (code "146") (name "/TDO_SOFT_B#") (class "Default")
      (node (ref "HDR7") (pin "6") (pinfunction "6_6") (pintype "passive"))
      (node (ref "RA30") (pin "3") (pintype "passive"))
    )
    (net (code "147") (name "/TMS") (class "Default")
      (node (ref "U8") (pin "76") (pinfunction "I/O_76") (pintype "bidirectional"))
    )
    (net (code "148") (name "/TMS_HARD") (class "Default")
      (node (ref "RA27") (pin "8") (pintype "passive"))
      (node (ref "RA31") (pin "8") (pintype "passive"))
      (node (ref "RA32") (pin "1") (pintype "passive"))
      (node (ref "U8") (pin "116") (pinfunction "I/O_116") (pintype "bidirectional"))
    )
    (net (code "149") (name "/TMS_HARD_A#") (class "Default")
      (node (ref "HDR6") (pin "4") (pinfunction "4_4") (pintype "passive"))
      (node (ref "RA27") (pin "1") (pintype "passive"))
    )
    (net (code "150") (name "/TMS_HARD_B#") (class "Default")
      (node (ref "HDR7") (pin "4") (pinfunction "4_4") (pintype "passive"))
      (node (ref "RA31") (pin "1") (pintype "passive"))
    )
    (net (code "151") (name "/TMS_SOFT_A") (class "Default")
      (node (ref "RA25") (pin "3") (pintype "passive"))
      (node (ref "RA26") (pin "8") (pintype "passive"))
      (node (ref "U8") (pin "112") (pinfunction "I/O_(~{CS}),_L5P_YY_112") (pintype "bidirectional"))
    )
    (net (code "152") (name "/TMS_SOFT_A#") (class "Default")
      (node (ref "HDR6") (pin "8") (pinfunction "8_8") (pintype "passive"))
      (node (ref "RA26") (pin "1") (pintype "passive"))
    )
    (net (code "153") (name "/TMS_SOFT_B") (class "Default")
      (node (ref "RA29") (pin "1") (pintype "passive"))
      (node (ref "RA30") (pin "8") (pintype "passive"))
      (node (ref "U8") (pin "122") (pinfunction "I/O,_L3N_YY_122") (pintype "bidirectional"))
    )
    (net (code "154") (name "/TMS_SOFT_B#") (class "Default")
      (node (ref "HDR7") (pin "8") (pinfunction "8_8") (pintype "passive"))
      (node (ref "RA30") (pin "1") (pintype "passive"))
    )
    (net (code "155") (name "/TP_U8-47") (class "Default")
      (node (ref "U8") (pin "47") (pinfunction "I/O,_L18N_YY_47") (pintype "bidirectional"))
    )
    (net (code "156") (name "/TP_U8-48") (class "Default")
      (node (ref "U8") (pin "48") (pinfunction "I/O,_L18P_YY_48") (pintype "bidirectional"))
    )
    (net (code "157") (name "5V") (class "Default")
      (node (ref "R5") (pin "1") (pinfunction "1_1") (pintype "passive"))
    )
    (net (code "158") (name "GND") (class "Default")
      (node (ref "C19") (pin "1") (pinfunction "1_1") (pintype "passive"))
      (node (ref "C20") (pin "2") (pinfunction "2_2") (pintype "passive"))
      (node (ref "C77") (pin "2") (pinfunction "2_2") (pintype "passive"))
      (node (ref "C78") (pin "2") (pinfunction "2_2") (pintype "passive"))
      (node (ref "C79") (pin "2") (pinfunction "2_2") (pintype "passive"))
      (node (ref "C80") (pin "2") (pinfunction "2_2") (pintype "passive"))
      (node (ref "HDR1") (pin "10") (pinfunction "10_10") (pintype "passive"))
      (node (ref "HDR1") (pin "7") (pinfunction "7_7") (pintype "passive"))
      (node (ref "HDR2") (pin "10") (pinfunction "10_10") (pintype "passive"))
      (node (ref "HDR2") (pin "2") (pinfunction "2_2") (pintype "passive"))
      (node (ref "HDR2") (pin "4") (pinfunction "4_4") (pintype "passive"))
      (node (ref "HDR2") (pin "6") (pinfunction "6_6") (pintype "passive"))
      (node (ref "HDR2") (pin "8") (pinfunction "8_8") (pintype "passive"))
      (node (ref "HDR4") (pin "7") (pinfunction "7_7") (pintype "passive"))
      (node (ref "HDR4") (pin "9") (pinfunction "9_9") (pintype "passive"))
      (node (ref "HDR5") (pin "10") (pinfunction "10_10") (pintype "passive"))
      (node (ref "HDR5") (pin "2") (pinfunction "2_2") (pintype "passive"))
      (node (ref "HDR5") (pin "4") (pinfunction "4_4") (pintype "passive"))
      (node (ref "HDR5") (pin "6") (pinfunction "6_6") (pintype "passive"))
      (node (ref "HDR5") (pin "8") (pinfunction "8_8") (pintype "passive"))
      (node (ref "HDR6") (pin "9") (pinfunction "9_9") (pintype "passive"))
      (node (ref "HDR7") (pin "9") (pinfunction "9_9") (pintype "passive"))
      (node (ref "LED10") (pin "2") (pinfunction "K_2") (pintype "passive"))
      (node (ref "LED11") (pin "2") (pinfunction "K_2") (pintype "passive"))
      (node (ref "LED12") (pin "2") (pinfunction "K_2") (pintype "passive"))
      (node (ref "LED13") (pin "2") (pinfunction "K_2") (pintype "passive"))
      (node (ref "LED14") (pin "2") (pinfunction "K_2") (pintype "passive"))
      (node (ref "LED15") (pin "2") (pinfunction "K_2") (pintype "passive"))
      (node (ref "LED16") (pin "2") (pinfunction "K_2") (pintype "passive"))
      (node (ref "LED8") (pin "2") (pinfunction "K_2") (pintype "passive"))
      (node (ref "LED9") (pin "2") (pinfunction "K_2") (pintype "passive"))
      (node (ref "R44") (pin "1") (pinfunction "1_1") (pintype "passive"))
      (node (ref "U6") (pin "4") (pinfunction "VSS_4") (pintype "power_in"))
      (node (ref "U7") (pin "4") (pinfunction "VSS_4") (pintype "power_in"))
      (node (ref "U8") (pin "52") (pinfunction "GCK1,_I_52") (pintype "input"))
      (node (ref "U8") (pin "55") (pinfunction "GCK0,_I_55") (pintype "input"))
    )
    (net (code "159") (name "Net-(LED8-A)") (class "Default")
      (node (ref "LED8") (pin "1") (pinfunction "A_1") (pintype "passive"))
      (node (ref "R5") (pin "2") (pinfunction "2_2") (pintype "passive"))
    )
    (net (code "160") (name "VCC") (class "Default")
      (node (ref "C19") (pin "2") (pinfunction "2_2") (pintype "passive"))
      (node (ref "C20") (pin "1") (pinfunction "1_1") (pintype "passive"))
      (node (ref "HDR5") (pin "9") (pinfunction "9_9") (pintype "passive"))
      (node (ref "R20") (pin "1") (pinfunction "1_1") (pintype "passive"))
      (node (ref "R21") (pin "1") (pinfunction "1_1") (pintype "passive"))
      (node (ref "R7") (pin "1") (pinfunction "1_1") (pintype "passive"))
      (node (ref "RA1") (pin "1") (pintype "passive"))
      (node (ref "RA1") (pin "2") (pintype "passive"))
      (node (ref "RA1") (pin "3") (pintype "passive"))
      (node (ref "RA1") (pin "4") (pintype "passive"))
      (node (ref "RA25") (pin "5") (pintype "passive"))
      (node (ref "RA25") (pin "6") (pintype "passive"))
      (node (ref "RA25") (pin "7") (pintype "passive"))
      (node (ref "RA25") (pin "8") (pintype "passive"))
      (node (ref "RA28") (pin "5") (pintype "passive"))
      (node (ref "RA28") (pin "6") (pintype "passive"))
      (node (ref "RA28") (pin "7") (pintype "passive"))
      (node (ref "RA28") (pin "8") (pintype "passive"))
      (node (ref "RA29") (pin "5") (pintype "passive"))
      (node (ref "RA29") (pin "6") (pintype "passive"))
      (node (ref "RA29") (pin "7") (pintype "passive"))
      (node (ref "RA29") (pin "8") (pintype "passive"))
      (node (ref "RA32") (pin "5") (pintype "passive"))
      (node (ref "RA32") (pin "6") (pintype "passive"))
      (node (ref "RA32") (pin "7") (pintype "passive"))
      (node (ref "RA32") (pin "8") (pintype "passive"))
      (node (ref "U6") (pin "3") (pinfunction "~{W}_3") (pintype "input"))
      (node (ref "U6") (pin "7") (pinfunction "HOL~{D}_7") (pintype "input"))
      (node (ref "U6") (pin "8") (pinfunction "VCC_8") (pintype "power_in"))
      (node (ref "U7") (pin "3") (pinfunction "~{W}_3") (pintype "input"))
      (node (ref "U7") (pin "7") (pinfunction "HOL~{D}_7") (pintype "input"))
      (node (ref "U7") (pin "8") (pinfunction "VCC_8") (pintype "power_in"))
    )
    (net (code "161") (name "unconnected-(HDR1-Pad5)") (class "Default")
      (node (ref "HDR1") (pin "5") (pinfunction "5_5") (pintype "passive"))
    )
    (net (code "162") (name "unconnected-(HDR1-Pad8)") (class "Default")
      (node (ref "HDR1") (pin "8") (pinfunction "8_8") (pintype "passive"))
    )
    (net (code "163") (name "unconnected-(HDR2-Pad9)") (class "Default")
      (node (ref "HDR2") (pin "9") (pinfunction "9_9") (pintype "passive"))
    )
    (net (code "164") (name "unconnected-(HDR4-Pad5)") (class "Default")
      (node (ref "HDR4") (pin "5") (pinfunction "5_5") (pintype "passive"))
    )
    (net (code "165") (name "unconnected-(HDR4-Pad8)") (class "Default")
      (node (ref "HDR4") (pin "8") (pinfunction "8_8") (pintype "passive"))
    )
    (net (code "166") (name "unconnected-(RA13-Pad4)") (class "Default")
      (node (ref "RA13") (pin "4") (pintype "passive"))
    )
    (net (code "167") (name "unconnected-(RA13-Pad5)") (class "Default")
      (node (ref "RA13") (pin "5") (pintype "passive"))
    )
  )
)
